# Nido.net
KiCad netlist of a schematic drawn in EAGLE
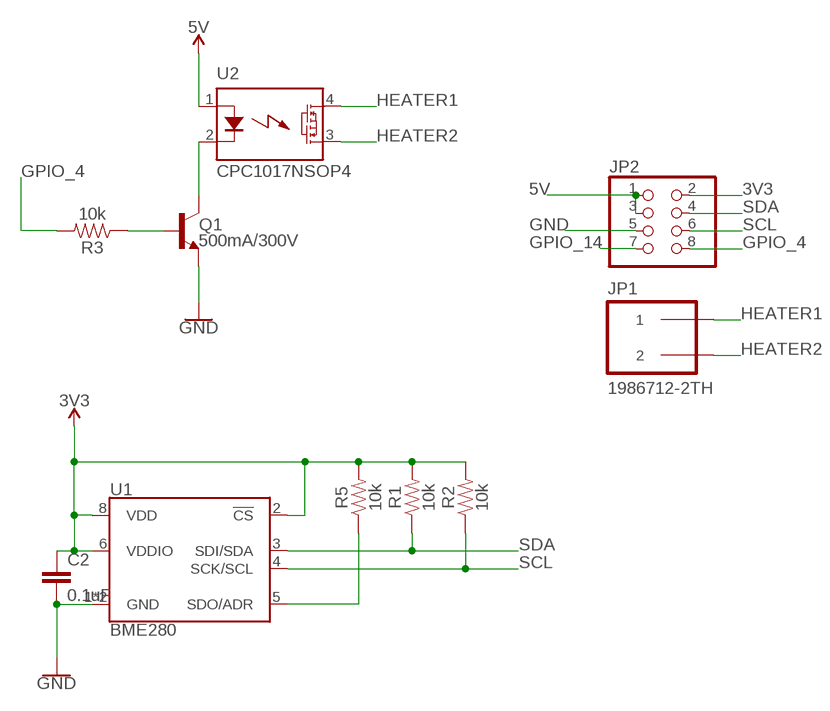
[diagram p0: schematic, sheet 1]

(export (version "E")
  (design (tool "Eeschema 10.0.6"))
  (components
    (comp (ref "C2")
      (value "0.1uF")
      (footprint "eagle-import:0402")
      (libsource (lib "eagle-import") (part "0.1UF-0402-16V-10%"))
    )
    (comp (ref "JP1")
      (value "1986712-2TH")
      (footprint "eagle-import:1986712-2")
      (libsource (lib "eagle-import") (part "1986712-2TH"))
    )
    (comp (ref "JP2")
      (value "PINHD-2X4")
      (footprint "eagle-import:2X04")
      (libsource (lib "eagle-import") (part "PINHD-2X4"))
    )
    (comp (ref "Q1")
      (value "500mA/300V")
      (footprint "eagle-import:SOT23-3")
      (libsource (lib "eagle-import") (part "TRANS_NPN-MMBTA42"))
    )
    (comp (ref "R1")
      (value "10k")
      (footprint "eagle-import:0402")
      (libsource (lib "eagle-import") (part "10KOHM-0402-1/16W-1%"))
    )
    (comp (ref "R2")
      (value "10k")
      (footprint "eagle-import:0402")
      (libsource (lib "eagle-import") (part "10KOHM-0402-1/16W-1%"))
    )
    (comp (ref "R3")
      (value "10k")
      (footprint "eagle-import:0402")
      (libsource (lib "eagle-import") (part "10KOHM-0402-1/16W-1%"))
    )
    (comp (ref "R5")
      (value "10k")
      (footprint "eagle-import:0402")
      (libsource (lib "eagle-import") (part "10KOHM-0402-1/16W-1%"))
    )
    (comp (ref "U1")
      (value "BME280")
      (footprint "eagle-import:LGA-8-2.5X2.5")
      (libsource (lib "eagle-import") (part "BME280"))
    )
    (comp (ref "U2")
      (value "CPC1017NSOP4")
      (footprint "eagle-import:CPC1017N")
      (libsource (lib "eagle-import") (part "CPC1017NSOP4"))
    )
  )
  (nets
    (net (code "1") (name "/GPIO_4") (class "Default")
      (node (ref "JP2") (pin "8") (pinfunction "8_8") (pintype "passive"))
      (node (ref "R3") (pin "2") (pinfunction "2_2") (pintype "passive"))
    )
    (net (code "2") (name "/GPIO_14") (class "Default")
      (node (ref "JP2") (pin "7") (pinfunction "7_7") (pintype "passive"))
    )
    (net (code "3") (name "/HEATER1") (class "Default")
      (node (ref "JP1") (pin "P$1") (pinfunction "1_P$1") (pintype "bidirectional"))
      (node (ref "JP1") (pin "P$2") (pinfunction "1_P$2") (pintype "bidirectional"))
      (node (ref "U2") (pin "4") (pinfunction "LOAD2_4") (pintype "passive"))
    )
    (net (code "4") (name "/HEATER2") (class "Default")
      (node (ref "JP1") (pin "P$3") (pinfunction "2_P$3") (pintype "bidirectional"))
      (node (ref "JP1") (pin "P$4") (pinfunction "2_P$4") (pintype "bidirectional"))
      (node (ref "U2") (pin "3") (pinfunction "LOAD1_3") (pintype "passive"))
    )
    (net (code "5") (name "/SCL") (class "Default")
      (node (ref "JP2") (pin "6") (pinfunction "6_6") (pintype "passive"))
      (node (ref "R2") (pin "1") (pinfunction "1_1") (pintype "passive"))
      (node (ref "U1") (pin "4") (pinfunction "SCK/SCL_4") (pintype "bidirectional"))
    )
    (net (code "6") (name "/SDA") (class "Default")
      (node (ref "JP2") (pin "4") (pinfunction "4_4") (pintype "passive"))
      (node (ref "R1") (pin "1") (pinfunction "1_1") (pintype "passive"))
      (node (ref "U1") (pin "3") (pinfunction "SDI/SDA_3") (pintype "bidirectional"))
    )
    (net (code "7") (name "3V3") (class "Default")
      (node (ref "C2") (pin "1") (pinfunction "1_1") (pintype "passive"))
      (node (ref "JP2") (pin "2") (pinfunction "2_2") (pintype "passive"))
      (node (ref "R1") (pin "2") (pinfunction "2_2") (pintype "passive"))
      (node (ref "R2") (pin "2") (pinfunction "2_2") (pintype "passive"))
      (node (ref "R5") (pin "2") (pinfunction "2_2") (pintype "passive"))
      (node (ref "U1") (pin "2") (pinfunction "~{CS}_2") (pintype "bidirectional"))
      (node (ref "U1") (pin "6") (pinfunction "VDDIO_6") (pintype "bidirectional"))
      (node (ref "U1") (pin "8") (pinfunction "VDD_8") (pintype "bidirectional"))
    )
    (net (code "8") (name "5V") (class "Default")
      (node (ref "JP2") (pin "1") (pinfunction "1_1") (pintype "passive"))
      (node (ref "JP2") (pin "3") (pinfunction "3_3") (pintype "passive"))
      (node (ref "U2") (pin "1") (pinfunction "+CONTROL_1") (pintype "passive"))
    )
    (net (code "9") (name "GND") (class "Default")
      (node (ref "C2") (pin "2") (pinfunction "2_2") (pintype "passive"))
      (node (ref "JP2") (pin "5") (pinfunction "5_5") (pintype "passive"))
      (node (ref "Q1") (pin "2") (pinfunction "E_2") (pintype "passive"))
      (node (ref "U1") (pin "1") (pinfunction "GND_1") (pintype "bidirectional"))
      (node (ref "U1") (pin "7") (pinfunction "GND_7") (pintype "bidirectional"))
    )
    (net (code "10") (name "Net-(Q1-B)") (class "Default")
      (node (ref "Q1") (pin "1") (pinfunction "B_1") (pintype "passive"))
      (node (ref "R3") (pin "1") (pinfunction "1_1") (pintype "passive"))
    )
    (net (code "11") (name "Net-(Q1-C)") (class "Default")
      (node (ref "Q1") (pin "3") (pinfunction "C_3") (pintype "passive"))
      (node (ref "U2") (pin "2") (pinfunction "-CONTROL_2") (pintype "passive"))
    )
    (net (code "12") (name "Net-(U1-SDO{slash}ADR)") (class "Default")
      (node (ref "R5") (pin "1") (pinfunction "1_1") (pintype "passive"))
      (node (ref "U1") (pin "5") (pinfunction "SDO/ADR_5") (pintype "bidirectional"))
    )
  )
)
